# 01_MAIN.net
KiCad netlist of a schematic drawn in Altium Designer
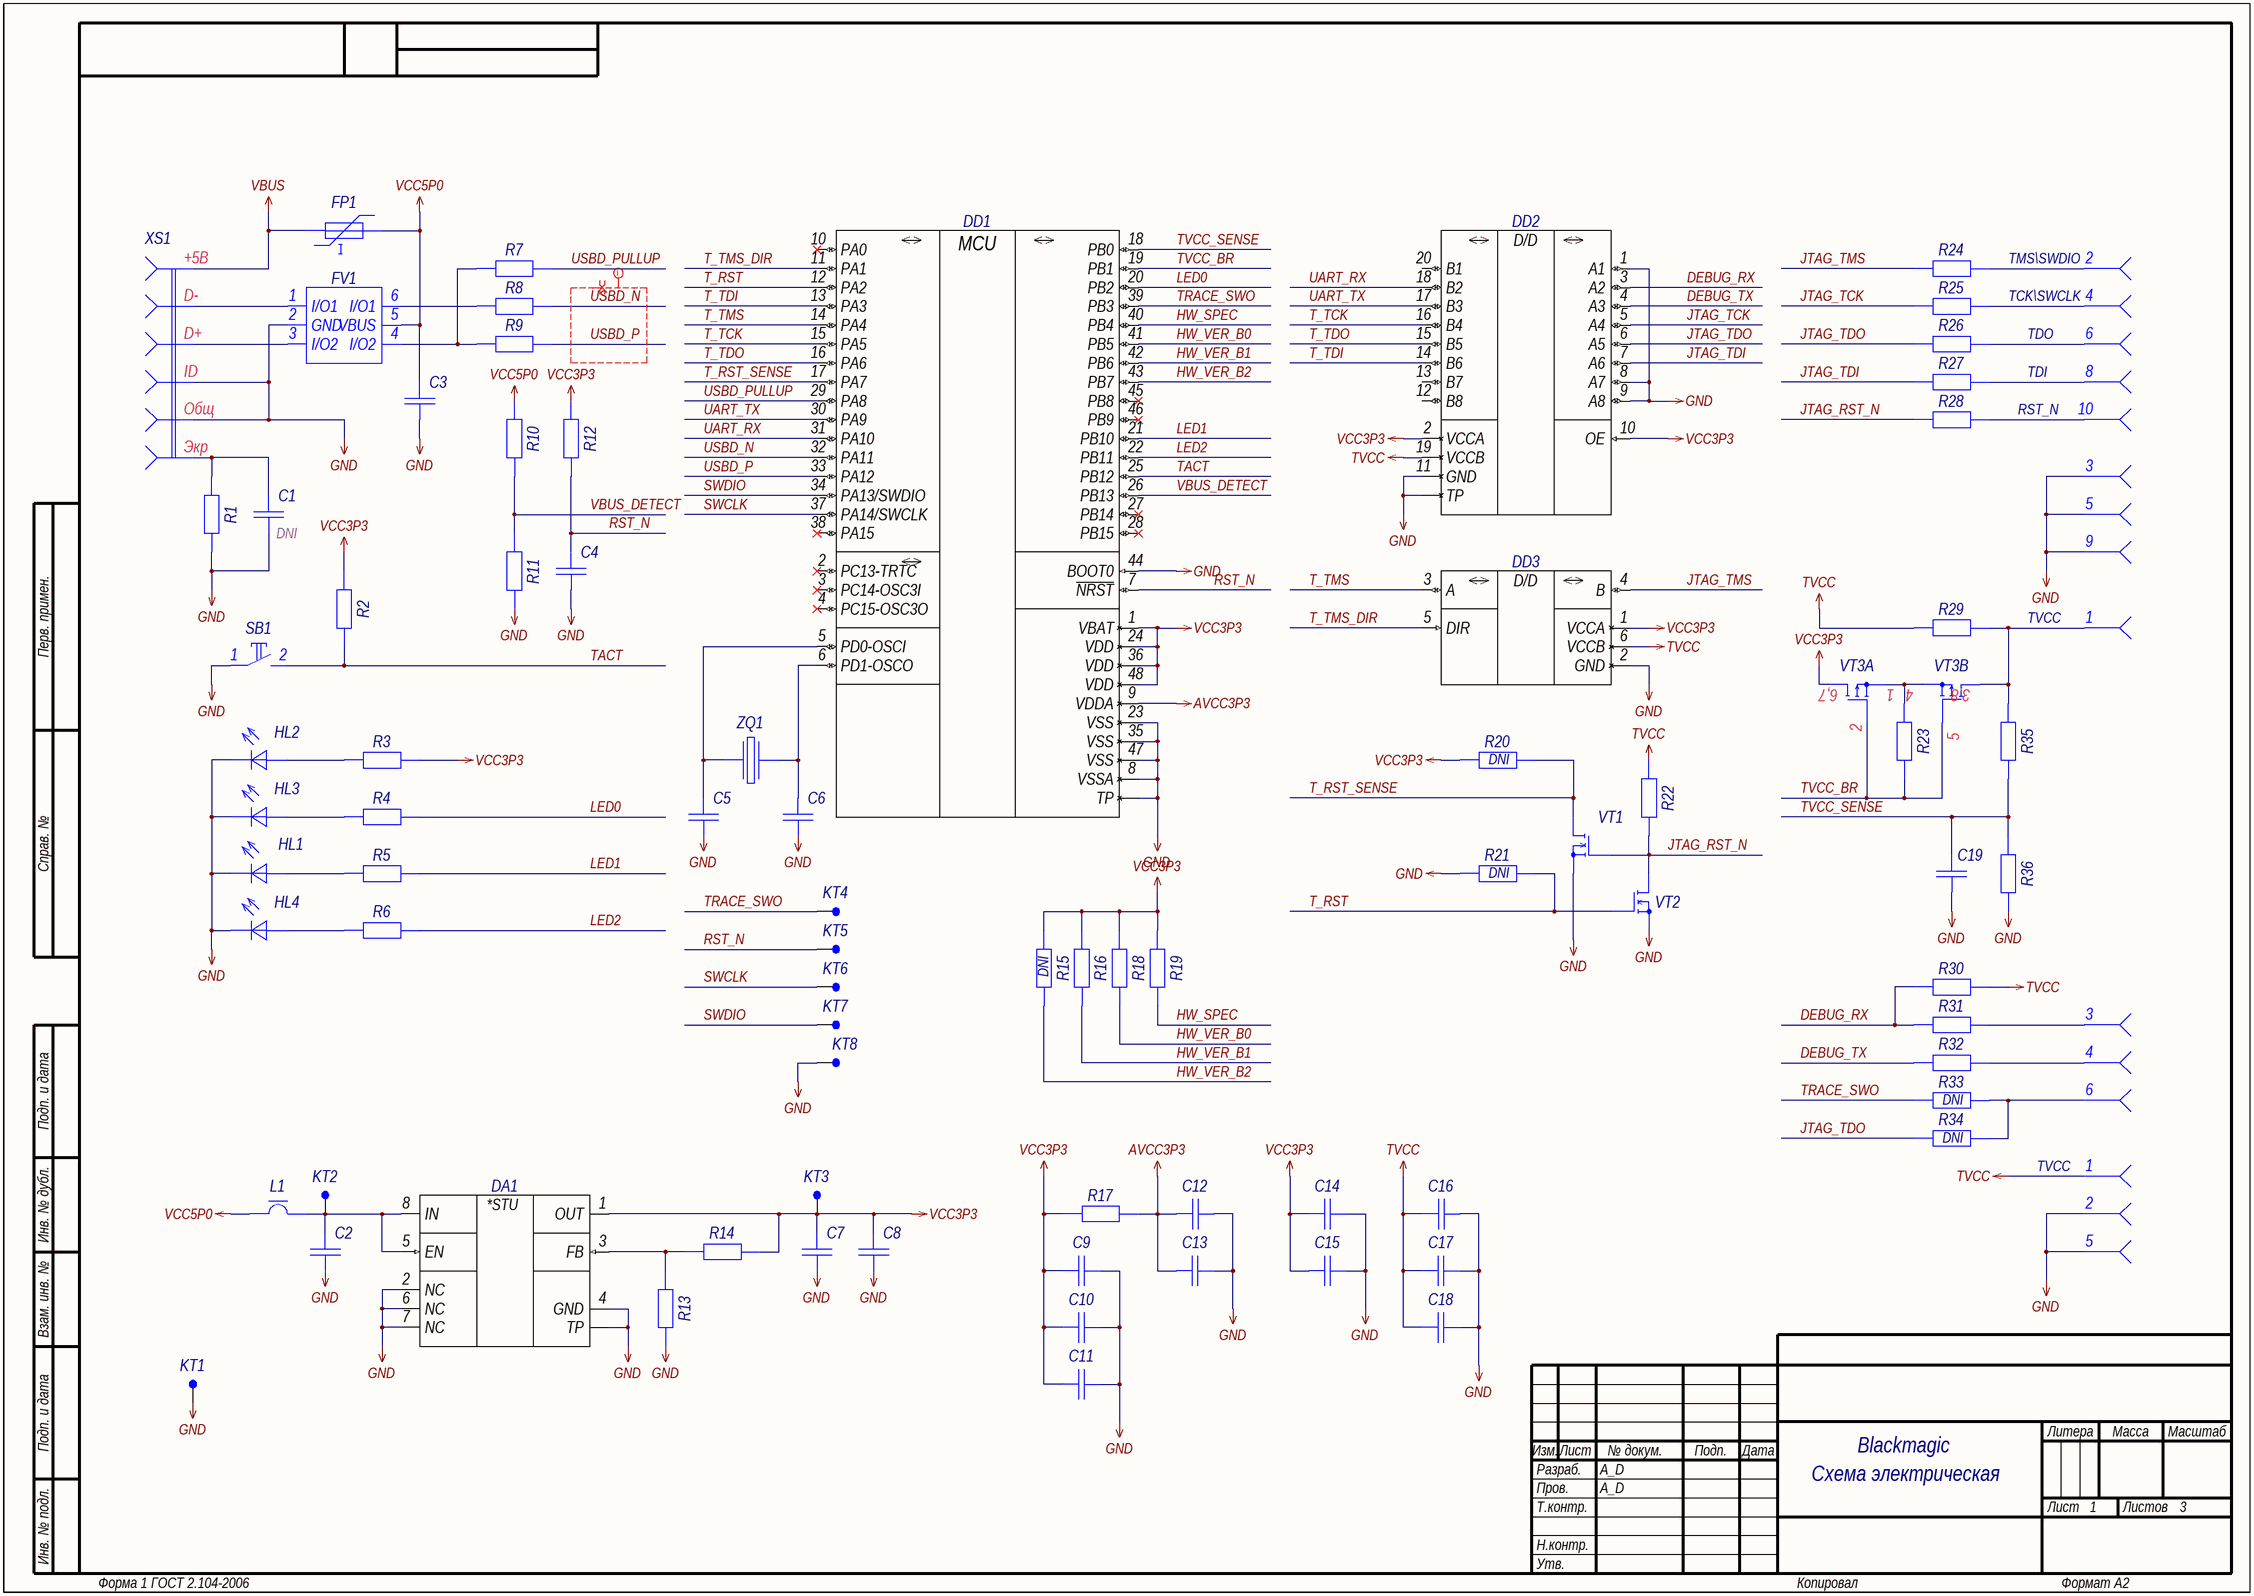
[diagram p0: 01_MAIN.SchDoc]

(export (version "E")
  (design (tool "Eeschema 10.0.6"))
  (components
    (comp (ref "C1")
      (value "Capacitor")
      (footprint "C0603_L")
      (fields
        (field (name "PART NUMBER") "GRM188R72A104KA35D")
        (field (name "VOLTAGE") "100V")
        (field (name "TOLERANCE") "±10%")
        (field (name "PUBLISHER") "Andrew Danich")
      )
      (libsource (lib "ADLib") (part "Capacitor"))
    )
    (comp (ref "C2")
      (value "Capacitor")
      (footprint "C0402_L")
      (fields
        (field (name "PART NUMBER") "GRM155R60J475ME87D")
        (field (name "VOLTAGE") "6.3V")
        (field (name "TOLERANCE") "±20%")
        (field (name "PUBLISHER") "Andrew Danich")
      )
      (libsource (lib "ADLib") (part "Capacitor"))
    )
    (comp (ref "C3")
      (value "Capacitor")
      (footprint "C0603_L")
      (fields
        (field (name "PART NUMBER") "GRM188R60J106ME47D")
        (field (name "VOLTAGE") "6.3V")
        (field (name "TOLERANCE") "±20%")
        (field (name "PUBLISHER") "Andrew Danich")
      )
      (libsource (lib "ADLib") (part "Capacitor"))
    )
    (comp (ref "C4")
      (value "Capacitor")
      (footprint "C0402_L")
      (fields
        (field (name "PART NUMBER") "GCM155R71C104KA55D")
        (field (name "VOLTAGE") "16V")
        (field (name "TOLERANCE") "±10%")
        (field (name "PUBLISHER") "Andrew Danich")
      )
      (libsource (lib "ADLib") (part "Capacitor"))
    )
    (comp (ref "C5")
      (value "Capacitor")
      (footprint "C0402_L")
      (fields
        (field (name "PART NUMBER") "GRM1555C1H150JA01D")
        (field (name "VOLTAGE") "50V")
        (field (name "TOLERANCE") "±5%")
        (field (name "PUBLISHER") "Andrew Danich")
      )
      (libsource (lib "ADLib") (part "Capacitor"))
    )
    (comp (ref "C6")
      (value "Capacitor")
      (footprint "C0402_L")
      (fields
        (field (name "PART NUMBER") "GRM1555C1H150JA01D")
        (field (name "VOLTAGE") "50V")
        (field (name "TOLERANCE") "±5%")
        (field (name "PUBLISHER") "Andrew Danich")
      )
      (libsource (lib "ADLib") (part "Capacitor"))
    )
    (comp (ref "C7")
      (value "Capacitor")
      (footprint "C0402_L")
      (fields
        (field (name "PART NUMBER") "GRM155R60J475ME87D")
        (field (name "VOLTAGE") "6.3V")
        (field (name "TOLERANCE") "±20%")
        (field (name "PUBLISHER") "Andrew Danich")
      )
      (libsource (lib "ADLib") (part "Capacitor"))
    )
    (comp (ref "C8")
      (value "Capacitor")
      (footprint "C0402_L")
      (fields
        (field (name "PART NUMBER") "GRM155R60J475ME87D")
        (field (name "VOLTAGE") "6.3V")
        (field (name "TOLERANCE") "±20%")
        (field (name "PUBLISHER") "Andrew Danich")
      )
      (libsource (lib "ADLib") (part "Capacitor"))
    )
    (comp (ref "C9")
      (value "Capacitor")
      (footprint "C0402_L")
      (fields
        (field (name "PART NUMBER") "GCM155R71C104KA55D")
        (field (name "VOLTAGE") "16V")
        (field (name "TOLERANCE") "±10%")
        (field (name "PUBLISHER") "Andrew Danich")
      )
      (libsource (lib "ADLib") (part "Capacitor"))
    )
    (comp (ref "C10")
      (value "Capacitor")
      (footprint "C0402_L")
      (fields
        (field (name "PART NUMBER") "GCM155R71C104KA55D")
        (field (name "VOLTAGE") "16V")
        (field (name "TOLERANCE") "±10%")
        (field (name "PUBLISHER") "Andrew Danich")
      )
      (libsource (lib "ADLib") (part "Capacitor"))
    )
    (comp (ref "C11")
      (value "Capacitor")
      (footprint "C0402_L")
      (fields
        (field (name "PART NUMBER") "GCM155R71C104KA55D")
        (field (name "VOLTAGE") "16V")
        (field (name "TOLERANCE") "±10%")
        (field (name "PUBLISHER") "Andrew Danich")
      )
      (libsource (lib "ADLib") (part "Capacitor"))
    )
    (comp (ref "C12")
      (value "Capacitor")
      (footprint "C0402_L")
      (fields
        (field (name "PART NUMBER") "GRM155C71A105KE11D")
        (field (name "VOLTAGE") "10V")
        (field (name "TOLERANCE") "±10%")
        (field (name "PUBLISHER") "Andrew Danich")
      )
      (libsource (lib "ADLib") (part "Capacitor"))
    )
    (comp (ref "C13")
      (value "Capacitor")
      (footprint "C0402_L")
      (fields
        (field (name "PART NUMBER") "GCM155R71C104KA55D")
        (field (name "VOLTAGE") "16V")
        (field (name "TOLERANCE") "±10%")
        (field (name "PUBLISHER") "Andrew Danich")
      )
      (libsource (lib "ADLib") (part "Capacitor"))
    )
    (comp (ref "C14")
      (value "Capacitor")
      (footprint "C0402_L")
      (fields
        (field (name "PART NUMBER") "GCM155R71C104KA55D")
        (field (name "VOLTAGE") "16V")
        (field (name "TOLERANCE") "±10%")
        (field (name "PUBLISHER") "Andrew Danich")
      )
      (libsource (lib "ADLib") (part "Capacitor"))
    )
    (comp (ref "C15")
      (value "Capacitor")
      (footprint "C0402_L")
      (fields
        (field (name "PART NUMBER") "GCM155R71C104KA55D")
        (field (name "VOLTAGE") "16V")
        (field (name "TOLERANCE") "±10%")
        (field (name "PUBLISHER") "Andrew Danich")
      )
      (libsource (lib "ADLib") (part "Capacitor"))
    )
    (comp (ref "C16")
      (value "Capacitor")
      (footprint "C0402_L")
      (fields
        (field (name "PART NUMBER") "GRM155C71A105KE11D")
        (field (name "VOLTAGE") "10V")
        (field (name "TOLERANCE") "±10%")
        (field (name "PUBLISHER") "Andrew Danich")
      )
      (libsource (lib "ADLib") (part "Capacitor"))
    )
    (comp (ref "C17")
      (value "Capacitor")
      (footprint "C0402_L")
      (fields
        (field (name "PART NUMBER") "GCM155R71C104KA55D")
        (field (name "VOLTAGE") "16V")
        (field (name "TOLERANCE") "±10%")
        (field (name "PUBLISHER") "Andrew Danich")
      )
      (libsource (lib "ADLib") (part "Capacitor"))
    )
    (comp (ref "C18")
      (value "Capacitor")
      (footprint "C0402_L")
      (fields
        (field (name "PART NUMBER") "GCM155R71C104KA55D")
        (field (name "VOLTAGE") "16V")
        (field (name "TOLERANCE") "±10%")
        (field (name "PUBLISHER") "Andrew Danich")
      )
      (libsource (lib "ADLib") (part "Capacitor"))
    )
    (comp (ref "C19")
      (value "Capacitor")
      (footprint "C0402_L")
      (fields
        (field (name "PART NUMBER") "GCM155R71C104KA55D")
        (field (name "VOLTAGE") "16V")
        (field (name "TOLERANCE") "±10%")
        (field (name "PUBLISHER") "Andrew Danich")
      )
      (libsource (lib "ADLib") (part "Capacitor"))
    )
    (comp (ref "DA1")
      (value "TPS73701DRB")
      (footprint "VSON-8_065P300X300X100_N")
      (fields
        (field (name "PART NUMBER") "TPS73701DRBR")
        (field (name "MANUFACTURER") "Texas Instruments")
        (field (name "PUBLISHER") "Andrew Danich")
      )
      (libsource (lib "ADLib") (part "TPS73701DRB"))
    )
    (comp (ref "DD1")
      (value "STM32F103CxUx-Series")
      (footprint "UFQFPN-48_050P700X700X060_N")
      (fields
        (field (name "PART NUMBER") "STM32F103CBU6")
        (field (name "MANUFACTURER") "STMicroelectronics")
        (field (name "PUBLISHER") "Andrew Danich")
      )
      (libsource (lib "ADLib") (part "STM32F103CxUx-Series"))
    )
    (comp (ref "DD2")
      (value "TXS0108ERGY")
      (footprint "VQFN-20_050P450X350X100_N")
      (fields
        (field (name "PART NUMBER") "TXS0108ERGYR")
        (field (name "MANUFACTURER") "Texas Instruments")
        (field (name "PUBLISHER") "Andrew Danich")
      )
      (libsource (lib "ADLib") (part "TXS0108ERGY"))
    )
    (comp (ref "DD3")
      (value "74LVC1T45x-Series")
      (footprint "X2-DFN-6_050P140X100X040_N")
      (fields
        (field (name "PART NUMBER") "74LVC1T45FZ4-7")
        (field (name "MANUFACTURER") "Diodes Incorporated")
        (field (name "PUBLISHER") "Andrew Danich")
      )
      (libsource (lib "ADLib") (part "74LVC1T45x-Series"))
    )
    (comp (ref "FP1")
      (value "Fuse_PTC")
      (footprint "F0603_L")
      (fields (field (name "PART NUMBER") "0603L100SLYR") (field (name "MANUFACTURER") "Littelfuse"))
      (libsource (lib "ADLib") (part "Fuse_PTC"))
    )
    (comp (ref "FV1")
      (value "USBLC6-2x6")
      (footprint "SOT-666_050P160X120X060_N")
      (fields
        (field (name "PART NUMBER") "USBLC6-2P6")
        (field (name "MANUFACTURER") "STMicroelectronics")
        (field (name "PUBLISHER") "Andrew Danich")
      )
      (libsource (lib "ADLib") (part "USBLC6-2x6"))
    )
    (comp (ref "HL1")
      (value "~")
      (footprint "LD0402_L")
      (fields
        (field (name "PART NUMBER") "KPHHS-1005SURCK")
        (field (name "MANUFACTURER") "Kingbright")
        (field (name "PUBLISHER") "Andrew Danich")
      )
      (libsource (lib "ADLib") (part "Led-1"))
    )
    (comp (ref "HL2")
      (value "Text")
      (footprint "LD0402_L")
      (fields
        (field (name "PART NUMBER") "KPHHS-1005CGCK")
        (field (name "MANUFACTURER") "Kingbright")
        (field (name "PUBLISHER") "Andrew Danich")
      )
      (libsource (lib "ADLib") (part "Led-1"))
    )
    (comp (ref "HL3")
      (value "Text")
      (footprint "LD0402_L")
      (fields
        (field (name "PART NUMBER") "KPHHS-1005CGCK")
        (field (name "MANUFACTURER") "Kingbright")
        (field (name "PUBLISHER") "Andrew Danich")
      )
      (libsource (lib "ADLib") (part "Led-1"))
    )
    (comp (ref "HL4")
      (value "~")
      (footprint "LD0402_L")
      (fields
        (field (name "PART NUMBER") "KPHHS-1005QBC-D-V")
        (field (name "MANUFACTURER") "Kingbright")
        (field (name "PUBLISHER") "Andrew Danich")
      )
      (libsource (lib "ADLib") (part "Led-1"))
    )
    (comp (ref "KT1")
      (value "Text")
      (footprint "TP-SMT-R-0.8mm")
      (fields (field (name "PART NUMBER") "TestPoint-SMT-GND") (field (name "PUBLISHER") "Andrew Danich"))
      (libsource (lib "ADLib") (part "TP-S-1"))
    )
    (comp (ref "KT2")
      (value "Text")
      (footprint "TP-SMT-C-0.5mm")
      (fields (field (name "PART NUMBER") "TestPoint-SMT") (field (name "PUBLISHER") "Andrew Danich"))
      (libsource (lib "ADLib") (part "TP-S-1"))
    )
    (comp (ref "KT3")
      (value "Text")
      (footprint "TP-SMT-C-0.5mm")
      (fields (field (name "PART NUMBER") "TestPoint-SMT") (field (name "PUBLISHER") "Andrew Danich"))
      (libsource (lib "ADLib") (part "TP-S-1"))
    )
    (comp (ref "KT4")
      (value "SWO")
      (footprint "TP-SMT-C-0.5mm")
      (fields (field (name "PART NUMBER") "TestPoint-SMT") (field (name "PUBLISHER") "Andrew Danich"))
      (libsource (lib "ADLib") (part "TP-S-1"))
    )
    (comp (ref "KT5")
      (value "SWO")
      (footprint "TP-SMT-C-0.5mm")
      (fields (field (name "PART NUMBER") "TestPoint-SMT") (field (name "PUBLISHER") "Andrew Danich"))
      (libsource (lib "ADLib") (part "TP-S-1"))
    )
    (comp (ref "KT6")
      (value "SWO")
      (footprint "TP-SMT-C-0.5mm")
      (fields (field (name "PART NUMBER") "TestPoint-SMT") (field (name "PUBLISHER") "Andrew Danich"))
      (libsource (lib "ADLib") (part "TP-S-1"))
    )
    (comp (ref "KT7")
      (value "SWO")
      (footprint "TP-SMT-C-0.5mm")
      (fields (field (name "PART NUMBER") "TestPoint-SMT") (field (name "PUBLISHER") "Andrew Danich"))
      (libsource (lib "ADLib") (part "TP-S-1"))
    )
    (comp (ref "KT8")
      (value "Text")
      (footprint "TP-SMT-R-0.8mm")
      (fields (field (name "PART NUMBER") "TestPoint-SMT-GND") (field (name "PUBLISHER") "Andrew Danich"))
      (libsource (lib "ADLib") (part "TP-S-1"))
    )
    (comp (ref "L1")
      (value "FerriteBead")
      (footprint "L0603_L")
      (fields
        (field (name "PART NUMBER") "BLM18PG121SN1")
        (field (name "TOLERANCE") "±25%")
        (field (name "MANUFACTURER") "Murata")
        (field (name "PUBLISHER") "Andrew Danich")
      )
      (libsource (lib "ADLib") (part "FerriteBead"))
    )
    (comp (ref "R1")
      (value "Resistor")
      (footprint "R0603_L")
      (fields
        (field (name "PART NUMBER") "RC0603JR-070R")
        (field (name "TOLERANCE") "±5%")
        (field (name "MANUFACTURER") "Yageo")
        (field (name "PUBLISHER") "Andrew Danich")
      )
      (libsource (lib "ADLib") (part "Resistor"))
    )
    (comp (ref "R2")
      (value "Resistor")
      (footprint "R0402_L")
      (fields
        (field (name "PART NUMBER") "RC0402JR-0710KL")
        (field (name "TOLERANCE") "±5%")
        (field (name "MANUFACTURER") "Yageo")
        (field (name "PUBLISHER") "Andrew Danich")
      )
      (libsource (lib "ADLib") (part "Resistor"))
    )
    (comp (ref "R3")
      (value "Resistor")
      (footprint "R0402_L")
      (fields
        (field (name "PART NUMBER") "RC0402JR-071KL")
        (field (name "TOLERANCE") "±5%")
        (field (name "MANUFACTURER") "Yageo")
        (field (name "PUBLISHER") "Andrew Danich")
      )
      (libsource (lib "ADLib") (part "Resistor"))
    )
    (comp (ref "R4")
      (value "Resistor")
      (footprint "R0402_L")
      (fields
        (field (name "PART NUMBER") "RC0402JR-071KL")
        (field (name "TOLERANCE") "±5%")
        (field (name "MANUFACTURER") "Yageo")
        (field (name "PUBLISHER") "Andrew Danich")
      )
      (libsource (lib "ADLib") (part "Resistor"))
    )
    (comp (ref "R5")
      (value "Resistor")
      (footprint "R0402_L")
      (fields
        (field (name "PART NUMBER") "RC0402JR-071KL")
        (field (name "TOLERANCE") "±5%")
        (field (name "MANUFACTURER") "Yageo")
        (field (name "PUBLISHER") "Andrew Danich")
      )
      (libsource (lib "ADLib") (part "Resistor"))
    )
    (comp (ref "R6")
      (value "Resistor")
      (footprint "R0402_L")
      (fields
        (field (name "PART NUMBER") "RC0402JR-071KL")
        (field (name "TOLERANCE") "±5%")
        (field (name "MANUFACTURER") "Yageo")
        (field (name "PUBLISHER") "Andrew Danich")
      )
      (libsource (lib "ADLib") (part "Resistor"))
    )
    (comp (ref "R7")
      (value "Resistor")
      (footprint "R0402_L")
      (fields
        (field (name "PART NUMBER") "RC0402FR-071K6L")
        (field (name "TOLERANCE") "±1%")
        (field (name "MANUFACTURER") "Yageo")
        (field (name "PUBLISHER") "Andrew Danich")
      )
      (libsource (lib "ADLib") (part "Resistor"))
    )
    (comp (ref "R8")
      (value "Resistor")
      (footprint "R0402_L")
      (fields
        (field (name "PART NUMBER") "RC0402JR-0720RL")
        (field (name "TOLERANCE") "±5%")
        (field (name "MANUFACTURER") "Yageo")
        (field (name "PUBLISHER") "Andrew Danich")
      )
      (libsource (lib "ADLib") (part "Resistor"))
    )
    (comp (ref "R9")
      (value "Resistor")
      (footprint "R0402_L")
      (fields
        (field (name "PART NUMBER") "RC0402JR-0720RL")
        (field (name "TOLERANCE") "±5%")
        (field (name "MANUFACTURER") "Yageo")
        (field (name "PUBLISHER") "Andrew Danich")
      )
      (libsource (lib "ADLib") (part "Resistor"))
    )
    (comp (ref "R10")
      (value "Resistor")
      (footprint "R0402_L")
      (fields
        (field (name "PART NUMBER") "RC0402JR-074K7L")
        (field (name "TOLERANCE") "±5%")
        (field (name "MANUFACTURER") "Yageo")
        (field (name "PUBLISHER") "Andrew Danich")
      )
      (libsource (lib "ADLib") (part "Resistor"))
    )
    (comp (ref "R11")
      (value "Resistor")
      (footprint "R0402_L")
      (fields
        (field (name "PART NUMBER") "RC0402JR-0710KL")
        (field (name "TOLERANCE") "±5%")
        (field (name "MANUFACTURER") "Yageo")
        (field (name "PUBLISHER") "Andrew Danich")
      )
      (libsource (lib "ADLib") (part "Resistor"))
    )
    (comp (ref "R12")
      (value "Resistor")
      (footprint "R0402_L")
      (fields
        (field (name "PART NUMBER") "RC0402JR-0710KL")
        (field (name "TOLERANCE") "±5%")
        (field (name "MANUFACTURER") "Yageo")
        (field (name "PUBLISHER") "Andrew Danich")
      )
      (libsource (lib "ADLib") (part "Resistor"))
    )
    (comp (ref "R13")
      (value "Resistor")
      (footprint "R0402_L")
      (fields
        (field (name "PART NUMBER") "RC0402FR-0712KL")
        (field (name "TOLERANCE") "±1%")
        (field (name "MANUFACTURER") "Yageo")
        (field (name "PUBLISHER") "Andrew Danich")
      )
      (libsource (lib "ADLib") (part "Resistor"))
    )
    (comp (ref "R14")
      (value "Resistor")
      (footprint "R0402_L")
      (fields
        (field (name "PART NUMBER") "RC0402FR-0722K1L")
        (field (name "TOLERANCE") "±1%")
        (field (name "MANUFACTURER") "Yageo")
        (field (name "PUBLISHER") "Andrew Danich")
      )
      (libsource (lib "ADLib") (part "Resistor"))
    )
    (comp (ref "R15")
      (value "Resistor")
      (footprint "R0402_L")
      (fields
        (field (name "PART NUMBER") "RC0402JR-070RL")
        (field (name "TOLERANCE") "±5%")
        (field (name "MANUFACTURER") "Yageo")
        (field (name "PUBLISHER") "Andrew Danich")
      )
      (libsource (lib "ADLib") (part "Resistor"))
    )
    (comp (ref "R16")
      (value "Resistor")
      (footprint "R0402_L")
      (fields
        (field (name "PART NUMBER") "RC0402JR-070RL")
        (field (name "TOLERANCE") "±5%")
        (field (name "MANUFACTURER") "Yageo")
        (field (name "PUBLISHER") "Andrew Danich")
      )
      (libsource (lib "ADLib") (part "Resistor"))
    )
    (comp (ref "R17")
      (value "Resistor")
      (footprint "R0402_L")
      (fields
        (field (name "PART NUMBER") "RC0402JR-070RL")
        (field (name "TOLERANCE") "±5%")
        (field (name "MANUFACTURER") "Yageo")
        (field (name "PUBLISHER") "Andrew Danich")
      )
      (libsource (lib "ADLib") (part "Resistor"))
    )
    (comp (ref "R18")
      (value "Resistor")
      (footprint "R0402_L")
      (fields
        (field (name "PART NUMBER") "RC0402JR-070RL")
        (field (name "TOLERANCE") "±5%")
        (field (name "MANUFACTURER") "Yageo")
        (field (name "PUBLISHER") "Andrew Danich")
      )
      (libsource (lib "ADLib") (part "Resistor"))
    )
    (comp (ref "R19")
      (value "Resistor")
      (footprint "R0402_L")
      (fields
        (field (name "PART NUMBER") "RC0402JR-070RL")
        (field (name "TOLERANCE") "±5%")
        (field (name "MANUFACTURER") "Yageo")
        (field (name "PUBLISHER") "Andrew Danich")
      )
      (libsource (lib "ADLib") (part "Resistor"))
    )
    (comp (ref "R20")
      (value "Resistor")
      (footprint "R0402_L")
      (fields
        (field (name "PART NUMBER") "RC0402JR-0710KL")
        (field (name "TOLERANCE") "±5%")
        (field (name "MANUFACTURER") "Yageo")
        (field (name "PUBLISHER") "Andrew Danich")
      )
      (libsource (lib "ADLib") (part "Resistor"))
    )
    (comp (ref "R21")
      (value "Resistor")
      (footprint "R0402_L")
      (fields
        (field (name "PART NUMBER") "RC0402JR-0710KL")
        (field (name "TOLERANCE") "±5%")
        (field (name "MANUFACTURER") "Yageo")
        (field (name "PUBLISHER") "Andrew Danich")
      )
      (libsource (lib "ADLib") (part "Resistor"))
    )
    (comp (ref "R22")
      (value "Resistor")
      (footprint "R0402_L")
      (fields
        (field (name "PART NUMBER") "RC0402JR-0710KL")
        (field (name "TOLERANCE") "±5%")
        (field (name "MANUFACTURER") "Yageo")
        (field (name "PUBLISHER") "Andrew Danich")
      )
      (libsource (lib "ADLib") (part "Resistor"))
    )
    (comp (ref "R23")
      (value "Resistor")
      (footprint "R0402_L")
      (fields
        (field (name "PART NUMBER") "RC0402JR-0710KL")
        (field (name "TOLERANCE") "±5%")
        (field (name "MANUFACTURER") "Yageo")
        (field (name "PUBLISHER") "Andrew Danich")
      )
      (libsource (lib "ADLib") (part "Resistor"))
    )
    (comp (ref "R24")
      (value "Resistor")
      (footprint "R0402_L")
      (fields
        (field (name "PART NUMBER") "RC0402JR-07100RL")
        (field (name "TOLERANCE") "±5%")
        (field (name "MANUFACTURER") "Yageo")
        (field (name "PUBLISHER") "Andrew Danich")
      )
      (libsource (lib "ADLib") (part "Resistor"))
    )
    (comp (ref "R25")
      (value "Resistor")
      (footprint "R0402_L")
      (fields
        (field (name "PART NUMBER") "RC0402JR-07100RL")
        (field (name "TOLERANCE") "±5%")
        (field (name "MANUFACTURER") "Yageo")
        (field (name "PUBLISHER") "Andrew Danich")
      )
      (libsource (lib "ADLib") (part "Resistor"))
    )
    (comp (ref "R26")
      (value "Resistor")
      (footprint "R0402_L")
      (fields
        (field (name "PART NUMBER") "RC0402JR-07100RL")
        (field (name "TOLERANCE") "±5%")
        (field (name "MANUFACTURER") "Yageo")
        (field (name "PUBLISHER") "Andrew Danich")
      )
      (libsource (lib "ADLib") (part "Resistor"))
    )
    (comp (ref "R27")
      (value "Resistor")
      (footprint "R0402_L")
      (fields
        (field (name "PART NUMBER") "RC0402JR-07100RL")
        (field (name "TOLERANCE") "±5%")
        (field (name "MANUFACTURER") "Yageo")
        (field (name "PUBLISHER") "Andrew Danich")
      )
      (libsource (lib "ADLib") (part "Resistor"))
    )
    (comp (ref "R28")
      (value "Resistor")
      (footprint "R0402_L")
      (fields
        (field (name "PART NUMBER") "RC0402JR-07100RL")
        (field (name "TOLERANCE") "±5%")
        (field (name "MANUFACTURER") "Yageo")
        (field (name "PUBLISHER") "Andrew Danich")
      )
      (libsource (lib "ADLib") (part "Resistor"))
    )
    (comp (ref "R29")
      (value "Resistor")
      (footprint "R0402_L")
      (fields
        (field (name "PART NUMBER") "RC0402JR-07100RL")
        (field (name "TOLERANCE") "±5%")
        (field (name "MANUFACTURER") "Yageo")
        (field (name "PUBLISHER") "Andrew Danich")
      )
      (libsource (lib "ADLib") (part "Resistor"))
    )
    (comp (ref "R30")
      (value "Resistor")
      (footprint "R0402_L")
      (fields
        (field (name "PART NUMBER") "RC0402JR-0710KL")
        (field (name "TOLERANCE") "±5%")
        (field (name "MANUFACTURER") "Yageo")
        (field (name "PUBLISHER") "Andrew Danich")
      )
      (libsource (lib "ADLib") (part "Resistor"))
    )
    (comp (ref "R31")
      (value "Resistor")
      (footprint "R0402_L")
      (fields
        (field (name "PART NUMBER") "RC0402JR-07100RL")
        (field (name "TOLERANCE") "±5%")
        (field (name "MANUFACTURER") "Yageo")
        (field (name "PUBLISHER") "Andrew Danich")
      )
      (libsource (lib "ADLib") (part "Resistor"))
    )
    (comp (ref "R32")
      (value "Resistor")
      (footprint "R0402_L")
      (fields
        (field (name "PART NUMBER") "RC0402JR-07100RL")
        (field (name "TOLERANCE") "±5%")
        (field (name "MANUFACTURER") "Yageo")
        (field (name "PUBLISHER") "Andrew Danich")
      )
      (libsource (lib "ADLib") (part "Resistor"))
    )
    (comp (ref "R33")
      (value "Resistor")
      (footprint "R0402_L")
      (fields
        (field (name "PART NUMBER") "RC0402JR-070RL")
        (field (name "TOLERANCE") "±5%")
        (field (name "MANUFACTURER") "Yageo")
        (field (name "PUBLISHER") "Andrew Danich")
      )
      (libsource (lib "ADLib") (part "Resistor"))
    )
    (comp (ref "R34")
      (value "Resistor")
      (footprint "R0402_L")
      (fields
        (field (name "PART NUMBER") "RC0402JR-070RL")
        (field (name "TOLERANCE") "±5%")
        (field (name "MANUFACTURER") "Yageo")
        (field (name "PUBLISHER") "Andrew Danich")
      )
      (libsource (lib "ADLib") (part "Resistor"))
    )
    (comp (ref "R35")
      (value "Resistor")
      (footprint "R0402_L")
      (fields
        (field (name "PART NUMBER") "RC0402JR-074K7L")
        (field (name "TOLERANCE") "±5%")
        (field (name "MANUFACTURER") "Yageo")
        (field (name "PUBLISHER") "Andrew Danich")
      )
      (libsource (lib "ADLib") (part "Resistor"))
    )
    (comp (ref "R36")
      (value "Resistor")
      (footprint "R0402_L")
      (fields
        (field (name "PART NUMBER") "RC0402JR-0710KL")
        (field (name "TOLERANCE") "±5%")
        (field (name "MANUFACTURER") "Yageo")
        (field (name "PUBLISHER") "Andrew Danich")
      )
      (libsource (lib "ADLib") (part "Resistor"))
    )
    (comp (ref "SB1")
      (value "~")
      (footprint "IT-1185AP")
      (fields (field (name "PART NUMBER") "IT-1185AP") (field (name "PUBLISHER") "Andrew Danich"))
      (libsource (lib "ADLib") (part "BT-01x-01p"))
    )
    (comp (ref "VT1")
      (value "MOSFET-N")
      (footprint "SOT-883B_035P060X100X040_N")
      (fields
        (field (name "PART NUMBER") "NX3008NBKMB")
        (field (name "MANUFACTURER") "NXP Semiconductors")
        (field (name "PUBLISHER") "Andrew Danich")
      )
      (libsource (lib "ADLib") (part "MOSFET-N"))
    )
    (comp (ref "VT2")
      (value "MOSFET-N")
      (footprint "SOT-883B_035P060X100X040_N")
      (fields
        (field (name "PART NUMBER") "NX3008NBKMB")
        (field (name "MANUFACTURER") "NXP Semiconductors")
        (field (name "PUBLISHER") "Andrew Danich")
      )
      (libsource (lib "ADLib") (part "MOSFET-N"))
    )
    (comp (ref "VT3")
      (value "MOSFET-PP_8p_2")
      (footprint "SOT-1118-2M_065P200X200X065_N")
      (fields
        (field (name "PART NUMBER") "PMDPB70XP")
        (field (name "MANUFACTURER") "NXP Semiconductors")
        (field (name "PUBLISHER") "Andrew Danich")
      )
      (libsource (lib "") (part "MOSFET-PP_8p_2_1"))
    )
    (comp (ref "XS1")
      (value "USB")
      (footprint "1981568-1")
      (fields
        (field (name "PART NUMBER") "1981568-1")
        (field (name "MANUFACTURER") "TE Connectivity")
        (field (name "PUBLISHER") "Andrew Danich")
      )
      (libsource (lib "ADLib") (part "Con-6-F-USB"))
    )
    (comp (ref "XS2")
      (value "JTAG")
      (footprint "XF2M-1015-1A")
      (fields
        (field (name "PART NUMBER") "XF2M-1015-1A")
        (field (name "MANUFACTURER") "Omron Electronics")
        (field (name "PUBLISHER") "Viktor Klishin")
      )
      (libsource (lib "ADLib") (part "Con-10-F_S"))
    )
    (comp (ref "XS3")
      (value "DEBUG")
      (footprint "XF2M-0615-1A")
      (fields
        (field (name "PART NUMBER") "XF2M-0615-1A")
        (field (name "MANUFACTURER") "Omron Electronics")
        (field (name "PUBLISHER") "Viktor Klishin")
      )
      (libsource (lib "ADLib") (part "Con-6-F_S"))
    )
    (comp (ref "ZQ1")
      (value "Crystal")
      (footprint "SMD 5x3.2mm")
      (fields
        (field (name "PART NUMBER") "KX-9A 8.0 MHz 30/50/100 16 pF")
        (field (name "MANUFACTURER") "Geyer")
        (field (name "PUBLISHER") "Andrew Danich")
      )
      (libsource (lib "ADLib") (part "Crystal"))
    )
  )
  (nets
    (net (code "1") (name "/DEBUG_RX") (class "Default")
      (node (ref "DD2") (pin "3") (pinfunction "A2_3") (pintype "bidirectional"))
      (node (ref "R30") (pin "2") (pinfunction "2_2") (pintype "passive"))
      (node (ref "R31") (pin "1") (pinfunction "1_1") (pintype "passive"))
    )
    (net (code "2") (name "/DEBUG_TX") (class "Default")
      (node (ref "DD2") (pin "4") (pinfunction "A3_4") (pintype "bidirectional"))
      (node (ref "R32") (pin "1") (pinfunction "1_1") (pintype "passive"))
    )
    (net (code "3") (name "/HW_SPEC") (class "Default")
      (node (ref "DD1") (pin "40") (pinfunction "PB4_40") (pintype "bidirectional"))
      (node (ref "R19") (pin "1") (pinfunction "1_1") (pintype "passive"))
    )
    (net (code "4") (name "/HW_VER_B0") (class "Default")
      (node (ref "DD1") (pin "41") (pinfunction "PB5_41") (pintype "bidirectional"))
      (node (ref "R18") (pin "1") (pinfunction "1_1") (pintype "passive"))
    )
    (net (code "5") (name "/HW_VER_B1") (class "Default")
      (node (ref "DD1") (pin "42") (pinfunction "PB6_42") (pintype "bidirectional"))
      (node (ref "R16") (pin "1") (pinfunction "1_1") (pintype "passive"))
    )
    (net (code "6") (name "/HW_VER_B2") (class "Default")
      (node (ref "DD1") (pin "43") (pinfunction "PB7_43") (pintype "bidirectional"))
      (node (ref "R15") (pin "1") (pinfunction "1_1") (pintype "passive"))
    )
    (net (code "7") (name "/JTAG_RST_N") (class "Default")
      (node (ref "R22") (pin "1") (pinfunction "1_1") (pintype "passive"))
      (node (ref "R28") (pin "1") (pinfunction "1_1") (pintype "passive"))
      (node (ref "VT1") (pin "1") (pinfunction "G_1") (pintype "passive"))
      (node (ref "VT2") (pin "2") (pinfunction "D_2") (pintype "passive"))
    )
    (net (code "8") (name "/JTAG_TCK") (class "Default")
      (node (ref "DD2") (pin "5") (pinfunction "A4_5") (pintype "bidirectional"))
      (node (ref "R25") (pin "1") (pinfunction "1_1") (pintype "passive"))
    )
    (net (code "9") (name "/JTAG_TDI") (class "Default")
      (node (ref "DD2") (pin "7") (pinfunction "A6_7") (pintype "bidirectional"))
      (node (ref "R27") (pin "1") (pinfunction "1_1") (pintype "passive"))
    )
    (net (code "10") (name "/JTAG_TDO") (class "Default")
      (node (ref "DD2") (pin "6") (pinfunction "A5_6") (pintype "bidirectional"))
      (node (ref "R26") (pin "1") (pinfunction "1_1") (pintype "passive"))
      (node (ref "R34") (pin "2") (pinfunction "2_2") (pintype "passive"))
    )
    (net (code "11") (name "/JTAG_TMS") (class "Default")
      (node (ref "DD3") (pin "4") (pinfunction "B_4") (pintype "bidirectional"))
      (node (ref "R24") (pin "1") (pinfunction "1_1") (pintype "passive"))
    )
    (net (code "12") (name "/LED0") (class "Default")
      (node (ref "DD1") (pin "20") (pinfunction "PB2_20") (pintype "bidirectional"))
      (node (ref "R4") (pin "2") (pinfunction "2_2") (pintype "passive"))
    )
    (net (code "13") (name "/LED1") (class "Default")
      (node (ref "DD1") (pin "21") (pinfunction "PB10_21") (pintype "bidirectional"))
      (node (ref "R5") (pin "2") (pinfunction "2_2") (pintype "passive"))
    )
    (net (code "14") (name "/LED2") (class "Default")
      (node (ref "DD1") (pin "22") (pinfunction "PB11_22") (pintype "bidirectional"))
      (node (ref "R6") (pin "2") (pinfunction "2_2") (pintype "passive"))
    )
    (net (code "15") (name "/RST_N") (class "Default")
      (node (ref "C4") (pin "2") (pinfunction "2_2") (pintype "passive"))
      (node (ref "DD1") (pin "7") (pinfunction "~{NRST}_7") (pintype "bidirectional"))
      (node (ref "KT5") (pin "1") (pinfunction "1_1") (pintype "passive"))
      (node (ref "R12") (pin "1") (pinfunction "1_1") (pintype "passive"))
    )
    (net (code "16") (name "/SWCLK") (class "Default")
      (node (ref "DD1") (pin "37") (pinfunction "PA14/SWCLK_37") (pintype "bidirectional"))
      (node (ref "KT6") (pin "1") (pinfunction "1_1") (pintype "passive"))
    )
    (net (code "17") (name "/SWDIO") (class "Default")
      (node (ref "DD1") (pin "34") (pinfunction "PA13/SWDIO_34") (pintype "bidirectional"))
      (node (ref "KT7") (pin "1") (pinfunction "1_1") (pintype "passive"))
    )
    (net (code "18") (name "/TACT") (class "Default")
      (node (ref "DD1") (pin "25") (pinfunction "PB12_25") (pintype "bidirectional"))
      (node (ref "R2") (pin "1") (pinfunction "1_1") (pintype "passive"))
      (node (ref "SB1") (pin "2") (pintype "passive"))
    )
    (net (code "19") (name "/TRACE_SWO") (class "Default")
      (node (ref "DD1") (pin "39") (pinfunction "PB3_39") (pintype "bidirectional"))
      (node (ref "KT4") (pin "1") (pinfunction "1_1") (pintype "passive"))
      (node (ref "R33") (pin "2") (pinfunction "2_2") (pintype "passive"))
    )
    (net (code "20") (name "/TVCC_BR") (class "Default")
      (node (ref "DD1") (pin "19") (pinfunction "PB1_19") (pintype "bidirectional"))
      (node (ref "R23") (pin "1") (pinfunction "1_1") (pintype "passive"))
      (node (ref "VT3") (pin "2") (pinfunction "G1_2") (pintype "passive"))
      (node (ref "VT3") (pin "5") (pinfunction "G2_5") (pintype "passive"))
    )
    (net (code "21") (name "/TVCC_SENSE") (class "Default")
      (node (ref "C19") (pin "2") (pinfunction "2_2") (pintype "passive"))
      (node (ref "DD1") (pin "18") (pinfunction "PB0_18") (pintype "bidirectional"))
      (node (ref "R35") (pin "1") (pinfunction "1_1") (pintype "passive"))
      (node (ref "R36") (pin "2") (pinfunction "2_2") (pintype "passive"))
    )
    (net (code "22") (name "/T_RST") (class "Default")
      (node (ref "DD1") (pin "12") (pinfunction "PA2_12") (pintype "bidirectional"))
      (node (ref "R21") (pin "1") (pinfunction "1_1") (pintype "passive"))
      (node (ref "VT2") (pin "1") (pinfunction "G_1") (pintype "passive"))
    )
    (net (code "23") (name "/T_RST_SENSE") (class "Default")
      (node (ref "DD1") (pin "17") (pinfunction "PA7_17") (pintype "bidirectional"))
      (node (ref "R20") (pin "1") (pinfunction "1_1") (pintype "passive"))
      (node (ref "VT1") (pin "2") (pinfunction "D_2") (pintype "passive"))
    )
    (net (code "24") (name "/T_TCK") (class "Default")
      (node (ref "DD1") (pin "15") (pinfunction "PA5_15") (pintype "bidirectional"))
      (node (ref "DD2") (pin "16") (pinfunction "B4_16") (pintype "bidirectional"))
    )
    (net (code "25") (name "/T_TDI") (class "Default")
      (node (ref "DD1") (pin "13") (pinfunction "PA3_13") (pintype "bidirectional"))
      (node (ref "DD2") (pin "14") (pinfunction "B6_14") (pintype "bidirectional"))
    )
    (net (code "26") (name "/T_TDO") (class "Default")
      (node (ref "DD1") (pin "16") (pinfunction "PA6_16") (pintype "bidirectional"))
      (node (ref "DD2") (pin "15") (pinfunction "B5_15") (pintype "bidirectional"))
    )
    (net (code "27") (name "/T_TMS") (class "Default")
      (node (ref "DD1") (pin "14") (pinfunction "PA4_14") (pintype "bidirectional"))
      (node (ref "DD3") (pin "3") (pinfunction "A_3") (pintype "bidirectional"))
    )
    (net (code "28") (name "/T_TMS_DIR") (class "Default")
      (node (ref "DD1") (pin "11") (pinfunction "PA1_11") (pintype "bidirectional"))
      (node (ref "DD3") (pin "5") (pinfunction "DIR_5") (pintype "input"))
    )
    (net (code "29") (name "/UART_RX") (class "Default")
      (node (ref "DD1") (pin "31") (pinfunction "PA10_31") (pintype "bidirectional"))
      (node (ref "DD2") (pin "18") (pinfunction "B2_18") (pintype "bidirectional"))
    )
    (net (code "30") (name "/UART_TX") (class "Default")
      (node (ref "DD1") (pin "30") (pinfunction "PA9_30") (pintype "bidirectional"))
      (node (ref "DD2") (pin "17") (pinfunction "B3_17") (pintype "bidirectional"))
    )
    (net (code "31") (name "/USBD_N") (class "Default")
      (node (ref "DD1") (pin "32") (pinfunction "PA11_32") (pintype "bidirectional"))
      (node (ref "R8") (pin "2") (pinfunction "2_2") (pintype "passive"))
    )
    (net (code "32") (name "/USBD_P") (class "Default")
      (node (ref "DD1") (pin "33") (pinfunction "PA12_33") (pintype "bidirectional"))
      (node (ref "R9") (pin "2") (pinfunction "2_2") (pintype "passive"))
    )
    (net (code "33") (name "/USBD_PULLUP") (class "Default")
      (node (ref "DD1") (pin "29") (pinfunction "PA8_29") (pintype "bidirectional"))
      (node (ref "R7") (pin "2") (pinfunction "2_2") (pintype "passive"))
    )
    (net (code "34") (name "/VBUS_DETECT") (class "Default")
      (node (ref "DD1") (pin "26") (pinfunction "PB13_26") (pintype "bidirectional"))
      (node (ref "R10") (pin "1") (pinfunction "1_1") (pintype "passive"))
      (node (ref "R11") (pin "2") (pinfunction "2_2") (pintype "passive"))
    )
    (net (code "35") (name "AVCC3P3") (class "Default")
      (node (ref "C12") (pin "1") (pinfunction "1_1") (pintype "passive"))
      (node (ref "C13") (pin "2") (pinfunction "2_2") (pintype "passive"))
      (node (ref "DD1") (pin "9") (pinfunction "VDDA_9") (pintype "power_in"))
      (node (ref "R17") (pin "1") (pinfunction "1_1") (pintype "passive"))
    )
    (net (code "36") (name "GND") (class "Default")
      (node (ref "C1") (pin "1") (pinfunction "1_1") (pintype "passive"))
      (node (ref "C10") (pin "1") (pinfunction "1_1") (pintype "passive"))
      (node (ref "C11") (pin "1") (pinfunction "1_1") (pintype "passive"))
      (node (ref "C12") (pin "2") (pinfunction "2_2") (pintype "passive"))
      (node (ref "C13") (pin "1") (pinfunction "1_1") (pintype "passive"))
      (node (ref "C14") (pin "1") (pinfunction "1_1") (pintype "passive"))
      (node (ref "C15") (pin "1") (pinfunction "1_1") (pintype "passive"))
      (node (ref "C16") (pin "2") (pinfunction "2_2") (pintype "passive"))
      (node (ref "C17") (pin "1") (pinfunction "1_1") (pintype "passive"))
      (node (ref "C18") (pin "1") (pinfunction "1_1") (pintype "passive"))
      (node (ref "C19") (pin "1") (pinfunction "1_1") (pintype "passive"))
      (node (ref "C2") (pin "1") (pinfunction "1_1") (pintype "passive"))
      (node (ref "C3") (pin "1") (pinfunction "1_1") (pintype "passive"))
      (node (ref "C4") (pin "1") (pinfunction "1_1") (pintype "passive"))
      (node (ref "C5") (pin "1") (pinfunction "1_1") (pintype "passive"))
      (node (ref "C6") (pin "1") (pinfunction "1_1") (pintype "passive"))
      (node (ref "C7") (pin "1") (pinfunction "1_1") (pintype "passive"))
      (node (ref "C8") (pin "1") (pinfunction "1_1") (pintype "passive"))
      (node (ref "C9") (pin "1") (pinfunction "1_1") (pintype "passive"))
      (node (ref "DA1") (pin "2") (pinfunction "NC_2") (pintype "passive"))
      (node (ref "DA1") (pin "4") (pinfunction "GND_4") (pintype "power_in"))
      (node (ref "DA1") (pin "6") (pinfunction "NC_6") (pintype "passive"))
      (node (ref "DA1") (pin "7") (pinfunction "NC_7") (pintype "passive"))
      (node (ref "DA1") (pin "TP") (pinfunction "TP_TP") (pintype "passive"))
      (node (ref "DD1") (pin "23") (pinfunction "VSS_23") (pintype "power_in"))
      (node (ref "DD1") (pin "35") (pinfunction "VSS_35") (pintype "power_in"))
      (node (ref "DD1") (pin "44") (pinfunction "BOOT0_44") (pintype "input"))
      (node (ref "DD1") (pin "47") (pinfunction "VSS_47") (pintype "power_in"))
      (node (ref "DD1") (pin "8") (pinfunction "VSSA_8") (pintype "power_in"))
      (node (ref "DD1") (pin "TP") (pinfunction "TP_TP") (pintype "power_in"))
      (node (ref "DD2") (pin "1") (pinfunction "A1_1") (pintype "bidirectional"))
      (node (ref "DD2") (pin "11") (pinfunction "GND_11") (pintype "power_in"))
      (node (ref "DD2") (pin "8") (pinfunction "A7_8") (pintype "bidirectional"))
      (node (ref "DD2") (pin "9") (pinfunction "A8_9") (pintype "bidirectional"))
      (node (ref "DD2") (pin "TP") (pinfunction "TP_TP") (pintype "power_in"))
      (node (ref "DD3") (pin "2") (pinfunction "GND_2") (pintype "power_in"))
      (node (ref "FV1") (pin "2") (pinfunction "GND_2") (pintype "passive"))
      (node (ref "HL1") (pin "2") (pinfunction "К_2") (pintype "passive"))
      (node (ref "HL2") (pin "2") (pinfunction "К_2") (pintype "passive"))
      (node (ref "HL3") (pin "2") (pinfunction "К_2") (pintype "passive"))
      (node (ref "HL4") (pin "2") (pinfunction "К_2") (pintype "passive"))
      (node (ref "KT1") (pin "1") (pinfunction "1_1") (pintype "passive"))
      (node (ref "KT8") (pin "1") (pinfunction "1_1") (pintype "passive"))
      (node (ref "R1") (pin "1") (pinfunction "1_1") (pintype "passive"))
      (node (ref "R11") (pin "1") (pinfunction "1_1") (pintype "passive"))
      (node (ref "R13") (pin "1") (pinfunction "1_1") (pintype "passive"))
      (node (ref "R21") (pin "2") (pinfunction "2_2") (pintype "passive"))
      (node (ref "R36") (pin "1") (pinfunction "1_1") (pintype "passive"))
      (node (ref "SB1") (pin "1") (pintype "passive"))
      (node (ref "VT1") (pin "3") (pinfunction "S_3") (pintype "passive"))
      (node (ref "VT2") (pin "3") (pinfunction "S_3") (pintype "passive"))
      (node (ref "XS1") (pin "4") (pintype "passive"))
      (node (ref "XS1") (pin "5") (pintype "passive"))
      (node (ref "XS2") (pin "3") (pintype "passive"))
      (node (ref "XS2") (pin "5") (pintype "passive"))
      (node (ref "XS2") (pin "9") (pintype "passive"))
      (node (ref "XS3") (pin "2") (pintype "passive"))
      (node (ref "XS3") (pin "5") (pintype "passive"))
    )
    (net (code "37") (name "Net-(C1-Pad2)") (class "Default")
      (node (ref "C1") (pin "2") (pinfunction "2_2") (pintype "passive"))
      (node (ref "R1") (pin "2") (pinfunction "2_2") (pintype "passive"))
      (node (ref "XS1") (pin "6") (pintype "passive"))
    )
    (net (code "38") (name "Net-(DA1-EN)") (class "Default")
      (node (ref "C2") (pin "2") (pinfunction "2_2") (pintype "passive"))
      (node (ref "DA1") (pin "5") (pinfunction "EN_5") (pintype "input"))
      (node (ref "DA1") (pin "8") (pinfunction "IN_8") (pintype "power_in"))
      (node (ref "KT2") (pin "1") (pinfunction "1_1") (pintype "passive"))
      (node (ref "L1") (pin "2") (pinfunction "2_2") (pintype "passive"))
    )
    (net (code "39") (name "Net-(DA1-FB)") (class "Default")
      (node (ref "DA1") (pin "3") (pinfunction "FB_3") (pintype "input"))
      (node (ref "R13") (pin "2") (pinfunction "2_2") (pintype "passive"))
      (node (ref "R14") (pin "1") (pinfunction "1_1") (pintype "passive"))
    )
    (net (code "40") (name "Net-(DD1-PD0-OSCI)") (class "Default")
      (node (ref "C5") (pin "2") (pinfunction "2_2") (pintype "passive"))
      (node (ref "DD1") (pin "5") (pinfunction "PD0-OSCI_5") (pintype "bidirectional"))
      (node (ref "ZQ1") (pin "3") (pinfunction "3_3") (pintype "passive"))
    )
    (net (code "41") (name "Net-(DD1-PD1-OSCO)") (class "Default")
      (node (ref "C6") (pin "2") (pinfunction "2_2") (pintype "passive"))
      (node (ref "DD1") (pin "6") (pinfunction "PD1-OSCO_6") (pintype "bidirectional"))
      (node (ref "ZQ1") (pin "1") (pinfunction "1_1") (pintype "passive"))
    )
    (net (code "42") (name "Net-(FV1-I{slash}O1-Pad1)") (class "Default")
      (node (ref "FV1") (pin "1") (pinfunction "I/O1_1") (pintype "passive"))
      (node (ref "XS1") (pin "2") (pintype "passive"))
    )
    (net (code "43") (name "Net-(FV1-I{slash}O1-Pad6)") (class "Default")
      (node (ref "FV1") (pin "6") (pinfunction "I/O1_6") (pintype "passive"))
      (node (ref "R8") (pin "1") (pinfunction "1_1") (pintype "passive"))
    )
    (net (code "44") (name "Net-(FV1-I{slash}O2-Pad3)") (class "Default")
      (node (ref "FV1") (pin "3") (pinfunction "I/O2_3") (pintype "passive"))
      (node (ref "XS1") (pin "3") (pintype "passive"))
    )
    (net (code "45") (name "Net-(FV1-I{slash}O2-Pad4)") (class "Default")
      (node (ref "FV1") (pin "4") (pinfunction "I/O2_4") (pintype "passive"))
      (node (ref "R7") (pin "1") (pinfunction "1_1") (pintype "passive"))
      (node (ref "R9") (pin "1") (pinfunction "1_1") (pintype "passive"))
    )
    (net (code "46") (name "Net-(HL1-А)") (class "Default")
      (node (ref "HL1") (pin "1") (pinfunction "А_1") (pintype "passive"))
      (node (ref "R5") (pin "1") (pinfunction "1_1") (pintype "passive"))
    )
    (net (code "47") (name "Net-(HL2-А)") (class "Default")
      (node (ref "HL2") (pin "1") (pinfunction "А_1") (pintype "passive"))
      (node (ref "R3") (pin "1") (pinfunction "1_1") (pintype "passive"))
    )
    (net (code "48") (name "Net-(HL3-А)") (class "Default")
      (node (ref "HL3") (pin "1") (pinfunction "А_1") (pintype "passive"))
      (node (ref "R4") (pin "1") (pinfunction "1_1") (pintype "passive"))
    )
    (net (code "49") (name "Net-(HL4-А)") (class "Default")
      (node (ref "HL4") (pin "1") (pinfunction "А_1") (pintype "passive"))
      (node (ref "R6") (pin "1") (pinfunction "1_1") (pintype "passive"))
    )
    (net (code "50") (name "Net-(R24-Pad2)") (class "Default")
      (node (ref "R24") (pin "2") (pinfunction "2_2") (pintype "passive"))
      (node (ref "XS2") (pin "2") (pintype "passive"))
    )
    (net (code "51") (name "Net-(R25-Pad2)") (class "Default")
      (node (ref "R25") (pin "2") (pinfunction "2_2") (pintype "passive"))
      (node (ref "XS2") (pin "4") (pintype "passive"))
    )
    (net (code "52") (name "Net-(R26-Pad2)") (class "Default")
      (node (ref "R26") (pin "2") (pinfunction "2_2") (pintype "passive"))
      (node (ref "XS2") (pin "6") (pintype "passive"))
    )
    (net (code "53") (name "Net-(R27-Pad2)") (class "Default")
      (node (ref "R27") (pin "2") (pinfunction "2_2") (pintype "passive"))
      (node (ref "XS2") (pin "8") (pintype "passive"))
    )
    (net (code "54") (name "Net-(R28-Pad2)") (class "Default")
      (node (ref "R28") (pin "2") (pinfunction "2_2") (pintype "passive"))
      (node (ref "XS2") (pin "10") (pintype "passive"))
    )
    (net (code "55") (name "Net-(R31-Pad2)") (class "Default")
      (node (ref "R31") (pin "2") (pinfunction "2_2") (pintype "passive"))
      (node (ref "XS3") (pin "3") (pintype "passive"))
    )
    (net (code "56") (name "Net-(R32-Pad2)") (class "Default")
      (node (ref "R32") (pin "2") (pinfunction "2_2") (pintype "passive"))
      (node (ref "XS3") (pin "4") (pintype "passive"))
    )
    (net (code "57") (name "Net-(R33-Pad1)") (class "Default")
      (node (ref "R33") (pin "1") (pinfunction "1_1") (pintype "passive"))
      (node (ref "R34") (pin "1") (pinfunction "1_1") (pintype "passive"))
      (node (ref "XS3") (pin "6") (pintype "passive"))
    )
    (net (code "58") (name "Net-(VT3A-S1)") (class "Default")
      (node (ref "R23") (pin "2") (pinfunction "2_2") (pintype "passive"))
      (node (ref "VT3") (pin "1") (pinfunction "S1_1") (pintype "passive"))
      (node (ref "VT3") (pin "4") (pinfunction "S2_4") (pintype "passive"))
    )
    (net (code "59") (name "Net-(VT3B-D2)") (class "Default")
      (node (ref "R29") (pin "2") (pinfunction "2_2") (pintype "passive"))
      (node (ref "R35") (pin "2") (pinfunction "2_2") (pintype "passive"))
      (node (ref "VT3") (pin "3") (pinfunction "D2_3") (pintype "passive"))
      (node (ref "XS2") (pin "1") (pintype "passive"))
    )
    (net (code "60") (name "TVCC") (class "Default")
      (node (ref "C16") (pin "1") (pinfunction "1_1") (pintype "passive"))
      (node (ref "C17") (pin "2") (pinfunction "2_2") (pintype "passive"))
      (node (ref "C18") (pin "2") (pinfunction "2_2") (pintype "passive"))
      (node (ref "DD2") (pin "19") (pinfunction "VCCB_19") (pintype "power_in"))
      (node (ref "DD3") (pin "6") (pinfunction "VCCB_6") (pintype "power_in"))
      (node (ref "R22") (pin "2") (pinfunction "2_2") (pintype "passive"))
      (node (ref "R29") (pin "1") (pinfunction "1_1") (pintype "passive"))
      (node (ref "R30") (pin "1") (pinfunction "1_1") (pintype "passive"))
      (node (ref "XS3") (pin "1") (pintype "passive"))
    )
    (net (code "61") (name "VBUS") (class "Default")
      (node (ref "FP1") (pin "1") (pinfunction "1_1") (pintype "passive"))
      (node (ref "XS1") (pin "1") (pintype "passive"))
    )
    (net (code "62") (name "VCC3P3") (class "Default")
      (node (ref "C10") (pin "2") (pinfunction "2_2") (pintype "passive"))
      (node (ref "C11") (pin "2") (pinfunction "2_2") (pintype "passive"))
      (node (ref "C14") (pin "2") (pinfunction "2_2") (pintype "passive"))
      (node (ref "C15") (pin "2") (pinfunction "2_2") (pintype "passive"))
      (node (ref "C7") (pin "2") (pinfunction "2_2") (pintype "passive"))
      (node (ref "C8") (pin "2") (pinfunction "2_2") (pintype "passive"))
      (node (ref "C9") (pin "2") (pinfunction "2_2") (pintype "passive"))
      (node (ref "DA1") (pin "1") (pinfunction "OUT_1") (pintype "power_in"))
      (node (ref "DD1") (pin "1") (pinfunction "VBAT_1") (pintype "power_in"))
      (node (ref "DD1") (pin "24") (pinfunction "VDD_24") (pintype "power_in"))
      (node (ref "DD1") (pin "36") (pinfunction "VDD_36") (pintype "power_in"))
      (node (ref "DD1") (pin "48") (pinfunction "VDD_48") (pintype "power_in"))
      (node (ref "DD2") (pin "10") (pinfunction "OE_10") (pintype "input"))
      (node (ref "DD2") (pin "2") (pinfunction "VCCA_2") (pintype "power_in"))
      (node (ref "DD3") (pin "1") (pinfunction "VCCA_1") (pintype "power_in"))
      (node (ref "KT3") (pin "1") (pinfunction "1_1") (pintype "passive"))
      (node (ref "R12") (pin "2") (pinfunction "2_2") (pintype "passive"))
      (node (ref "R14") (pin "2") (pinfunction "2_2") (pintype "passive"))
      (node (ref "R15") (pin "2") (pinfunction "2_2") (pintype "passive"))
      (node (ref "R16") (pin "2") (pinfunction "2_2") (pintype "passive"))
      (node (ref "R17") (pin "2") (pinfunction "2_2") (pintype "passive"))
      (node (ref "R18") (pin "2") (pinfunction "2_2") (pintype "passive"))
      (node (ref "R19") (pin "2") (pinfunction "2_2") (pintype "passive"))
      (node (ref "R2") (pin "2") (pinfunction "2_2") (pintype "passive"))
      (node (ref "R20") (pin "2") (pinfunction "2_2") (pintype "passive"))
      (node (ref "R3") (pin "2") (pinfunction "2_2") (pintype "passive"))
      (node (ref "VT3") (pin "6") (pinfunction "D1_6") (pintype "passive"))
    )
    (net (code "63") (name "VCC5P0") (class "Default")
      (node (ref "C3") (pin "2") (pinfunction "2_2") (pintype "passive"))
      (node (ref "FP1") (pin "2") (pinfunction "2_2") (pintype "passive"))
      (node (ref "FV1") (pin "5") (pinfunction "VBUS_5") (pintype "passive"))
      (node (ref "L1") (pin "1") (pinfunction "1_1") (pintype "passive"))
      (node (ref "R10") (pin "2") (pinfunction "2_2") (pintype "passive"))
    )
    (net (code "64") (name "unconnected-(DD1-PA0-Pad10)") (class "Default")
      (node (ref "DD1") (pin "10") (pinfunction "PA0_10") (pintype "bidirectional+no_connect"))
    )
    (net (code "65") (name "unconnected-(DD1-PA15-Pad38)") (class "Default")
      (node (ref "DD1") (pin "38") (pinfunction "PA15_38") (pintype "bidirectional+no_connect"))
    )
    (net (code "66") (name "unconnected-(DD1-PB8-Pad45)") (class "Default")
      (node (ref "DD1") (pin "45") (pinfunction "PB8_45") (pintype "bidirectional+no_connect"))
    )
    (net (code "67") (name "unconnected-(DD1-PB9-Pad46)") (class "Default")
      (node (ref "DD1") (pin "46") (pinfunction "PB9_46") (pintype "bidirectional+no_connect"))
    )
    (net (code "68") (name "unconnected-(DD1-PB14-Pad27)") (class "Default")
      (node (ref "DD1") (pin "27") (pinfunction "PB14_27") (pintype "bidirectional+no_connect"))
    )
    (net (code "69") (name "unconnected-(DD1-PB15-Pad28)") (class "Default")
      (node (ref "DD1") (pin "28") (pinfunction "PB15_28") (pintype "bidirectional+no_connect"))
    )
    (net (code "70") (name "unconnected-(DD1-PC13-TRTC-Pad2)") (class "Default")
      (node (ref "DD1") (pin "2") (pinfunction "PC13-TRTC_2") (pintype "bidirectional+no_connect"))
    )
    (net (code "71") (name "unconnected-(DD1-PC14-OSC3I-Pad3)") (class "Default")
      (node (ref "DD1") (pin "3") (pinfunction "PC14-OSC3I_3") (pintype "bidirectional+no_connect"))
    )
    (net (code "72") (name "unconnected-(DD1-PC15-OSC3O-Pad4)") (class "Default")
      (node (ref "DD1") (pin "4") (pinfunction "PC15-OSC3O_4") (pintype "bidirectional+no_connect"))
    )
    (net (code "73") (name "unconnected-(DD2-B1-Pad20)") (class "Default")
      (node (ref "DD2") (pin "20") (pinfunction "B1_20") (pintype "bidirectional"))
    )
    (net (code "74") (name "unconnected-(DD2-B7-Pad13)") (class "Default")
      (node (ref "DD2") (pin "13") (pinfunction "B7_13") (pintype "bidirectional"))
    )
    (net (code "75") (name "unconnected-(DD2-B8-Pad12)") (class "Default")
      (node (ref "DD2") (pin "12") (pinfunction "B8_12") (pintype "bidirectional"))
    )
  )
)
